# metium_rfm69.net
KiCad netlist of a schematic drawn in EAGLE
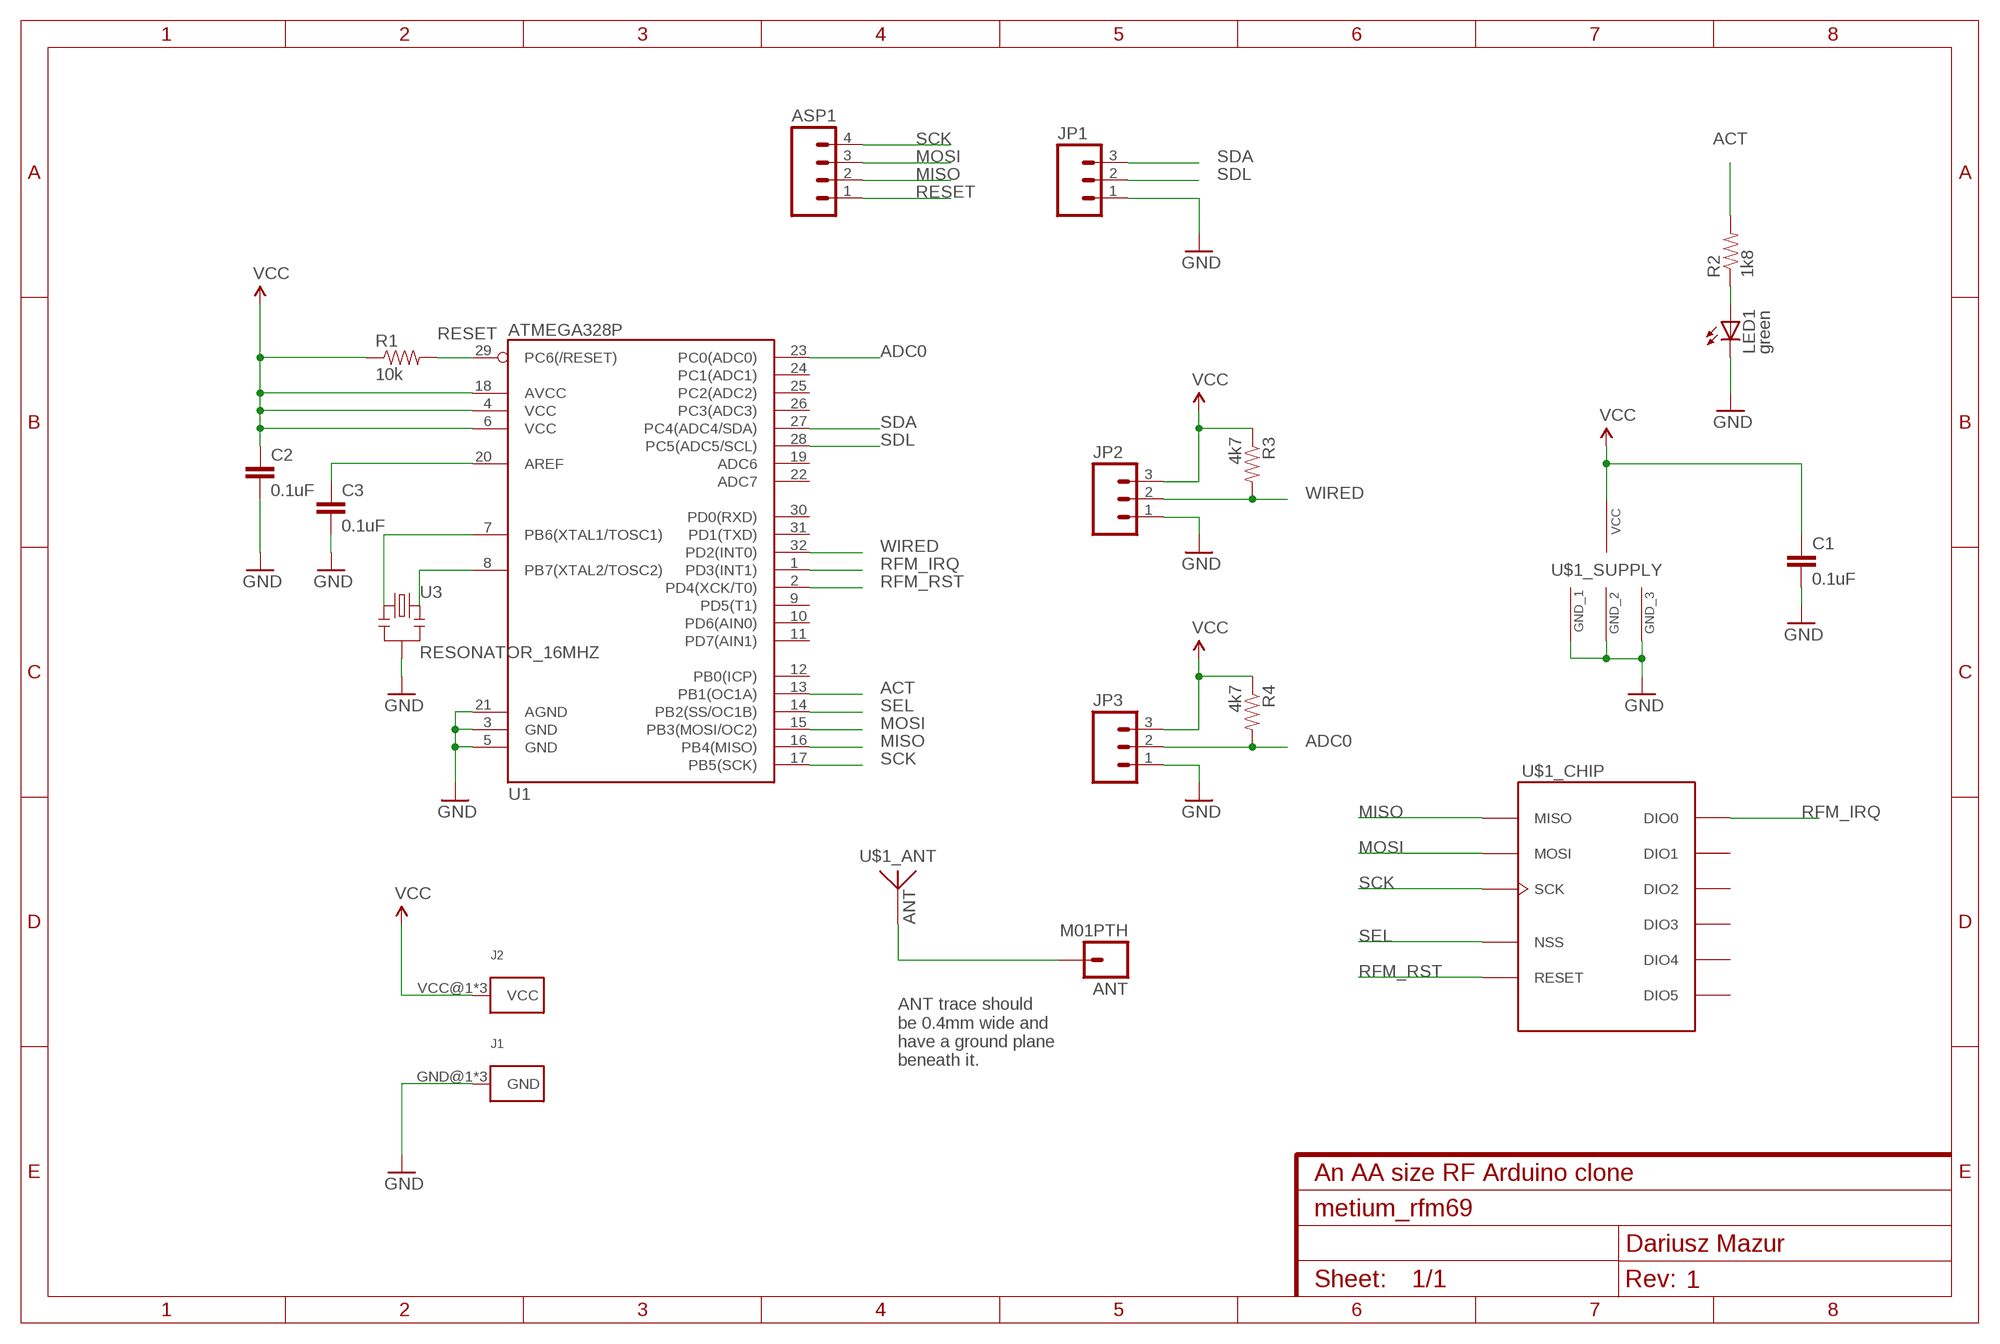
[diagram p0: schematic, sheet 1]

(export (version "E")
  (design (tool "Eeschema 10.0.6"))
  (components
    (comp (ref "ANT")
      (value "M01PTH")
      (footprint "eagle-import:1X01")
      (libsource (lib "eagle-import") (part "M01PTH"))
    )
    (comp (ref "ASP1")
      (value "M04PTH")
      (footprint "eagle-import:1X04")
      (libsource (lib "eagle-import") (part "M04PTH"))
    )
    (comp (ref "C1")
      (value "0.1uF")
      (footprint "eagle-import:0603-CAP")
      (libsource (lib "eagle-import") (part "0.1UF-25V(+80/-20%)(0603)"))
    )
    (comp (ref "C2")
      (value "0.1uF")
      (footprint "eagle-import:0603-CAP")
      (libsource (lib "eagle-import") (part "0.1UF-25V(+80/-20%)(0603)"))
    )
    (comp (ref "C3")
      (value "0.1uF")
      (footprint "eagle-import:0603-CAP")
      (libsource (lib "eagle-import") (part "0.1UF-25V(+80/-20%)(0603)"))
    )
    (comp (ref "J1")
      (value "KEYSTONE-629")
      (footprint "eagle-import:KEYSTONE_AA_AAA_BATTERY_TERMINAL-629")
      (libsource (lib "eagle-import") (part "KEYSTONE-629"))
    )
    (comp (ref "J2")
      (value "KEYSTONE-637")
      (footprint "eagle-import:KEYSTONE_AA_AAA_BATTERY_TERMINAL-637")
      (libsource (lib "eagle-import") (part "KEYSTONE-637"))
    )
    (comp (ref "JP1")
      (value "M03PTH")
      (footprint "eagle-import:1X03")
      (libsource (lib "eagle-import") (part "M03PTH"))
    )
    (comp (ref "JP2")
      (value "M03PTH")
      (footprint "eagle-import:1X03")
      (libsource (lib "eagle-import") (part "M03PTH"))
    )
    (comp (ref "JP3")
      (value "M03PTH")
      (footprint "eagle-import:1X03")
      (libsource (lib "eagle-import") (part "M03PTH"))
    )
    (comp (ref "LED1")
      (value "green")
      (footprint "eagle-import:LED-0603")
      (libsource (lib "eagle-import") (part "LED0603"))
    )
    (comp (ref "R1")
      (value "10k")
      (footprint "eagle-import:0603-RES")
      (libsource (lib "eagle-import") (part "RESISTOR0603-RES"))
    )
    (comp (ref "R2")
      (value "1k8")
      (footprint "eagle-import:0603-RES")
      (libsource (lib "eagle-import") (part "RESISTOR0603-RES"))
    )
    (comp (ref "R3")
      (value "4k7")
      (footprint "eagle-import:0603-RES")
      (libsource (lib "eagle-import") (part "RESISTOR0603-RES"))
    )
    (comp (ref "R4")
      (value "4k7")
      (footprint "eagle-import:0603-RES")
      (libsource (lib "eagle-import") (part "RESISTOR0603-RES"))
    )
    (comp (ref "U$1")
      (value "RFM69HCW-S2")
      (footprint "eagle-import:HOPE-RF-16")
      (libsource (lib "eagle-import") (part "RFM69HCW-S2"))
    )
    (comp (ref "U1")
      (value "ATMEGA328P")
      (footprint "eagle-import:TQFP32-08")
      (libsource (lib "eagle-import") (part "ATMEGA328_SMT"))
    )
    (comp (ref "U3")
      (value "RESONATOR_16MHZ")
      (footprint "eagle-import:RESONATOR_SMD")
      (libsource (lib "eagle-import") (part "RESONATOR_16MHZ"))
    )
  )
  (nets
    (net (code "1") (name "/ACT") (class "Default")
      (node (ref "R2") (pin "2") (pinfunction "2_2") (pintype "passive"))
      (node (ref "U1") (pin "13") (pinfunction "PB1(OC1A)_13") (pintype "bidirectional"))
    )
    (net (code "2") (name "/ADC0") (class "Default")
      (node (ref "JP3") (pin "2") (pinfunction "2_2") (pintype "passive"))
      (node (ref "R4") (pin "2") (pinfunction "2_2") (pintype "passive"))
      (node (ref "U1") (pin "23") (pinfunction "PC0(ADC0)_23") (pintype "bidirectional"))
    )
    (net (code "3") (name "/MISO") (class "Default")
      (node (ref "ASP1") (pin "2") (pinfunction "2_2") (pintype "passive"))
      (node (ref "U$1") (pin "MISO") (pinfunction "MISO_MISO") (pintype "input"))
      (node (ref "U1") (pin "16") (pinfunction "PB4(MISO)_16") (pintype "bidirectional"))
    )
    (net (code "4") (name "/MOSI") (class "Default")
      (node (ref "ASP1") (pin "3") (pinfunction "3_3") (pintype "passive"))
      (node (ref "U$1") (pin "MOSI") (pinfunction "MOSI_MOSI") (pintype "output"))
      (node (ref "U1") (pin "15") (pinfunction "PB3(MOSI/OC2)_15") (pintype "bidirectional"))
    )
    (net (code "5") (name "/RESET") (class "Default")
      (node (ref "ASP1") (pin "1") (pinfunction "1_1") (pintype "passive"))
      (node (ref "R1") (pin "2") (pinfunction "2_2") (pintype "passive"))
      (node (ref "U1") (pin "29") (pinfunction "PC6(/RESET)_29") (pintype "bidirectional"))
    )
    (net (code "6") (name "/RFM_IRQ") (class "Default")
      (node (ref "U$1") (pin "DIO0") (pinfunction "DIO0_DIO0") (pintype "bidirectional"))
      (node (ref "U1") (pin "1") (pinfunction "PD3(INT1)_1") (pintype "bidirectional"))
    )
    (net (code "7") (name "/RFM_RST") (class "Default")
      (node (ref "U$1") (pin "RESET") (pinfunction "RESET_RESET") (pintype "bidirectional"))
      (node (ref "U1") (pin "2") (pinfunction "PD4(XCK/T0)_2") (pintype "bidirectional"))
    )
    (net (code "8") (name "/SCK") (class "Default")
      (node (ref "ASP1") (pin "4") (pinfunction "4_4") (pintype "passive"))
      (node (ref "U$1") (pin "SCK") (pinfunction "SCK_SCK") (pintype "input"))
      (node (ref "U1") (pin "17") (pinfunction "PB5(SCK)_17") (pintype "bidirectional"))
    )
    (net (code "9") (name "/SDA") (class "Default")
      (node (ref "JP1") (pin "3") (pinfunction "3_3") (pintype "passive"))
      (node (ref "U1") (pin "27") (pinfunction "PC4(ADC4/SDA)_27") (pintype "bidirectional"))
    )
    (net (code "10") (name "/SDL") (class "Default")
      (node (ref "JP1") (pin "2") (pinfunction "2_2") (pintype "passive"))
      (node (ref "U1") (pin "28") (pinfunction "PC5(ADC5/SCL)_28") (pintype "bidirectional"))
    )
    (net (code "11") (name "/SEL") (class "Default")
      (node (ref "U$1") (pin "NSS") (pinfunction "NSS_NSS") (pintype "input"))
      (node (ref "U1") (pin "14") (pinfunction "PB2(SS/OC1B)_14") (pintype "bidirectional"))
    )
    (net (code "12") (name "/WIRED") (class "Default")
      (node (ref "JP2") (pin "2") (pinfunction "2_2") (pintype "passive"))
      (node (ref "R3") (pin "2") (pinfunction "2_2") (pintype "passive"))
      (node (ref "U1") (pin "32") (pinfunction "PD2(INT0)_32") (pintype "bidirectional"))
    )
    (net (code "13") (name "GND") (class "Default")
      (node (ref "C1") (pin "2") (pinfunction "2_2") (pintype "passive"))
      (node (ref "C2") (pin "2") (pinfunction "2_2") (pintype "passive"))
      (node (ref "C3") (pin "2") (pinfunction "2_2") (pintype "passive"))
      (node (ref "J1") (pin "GND@1") (pinfunction "GND_GND@1") (pintype "power_in"))
      (node (ref "J1") (pin "GND@2") (pinfunction "GND_GND@2") (pintype "power_in"))
      (node (ref "J1") (pin "GND@3") (pinfunction "GND_GND@3") (pintype "power_in"))
      (node (ref "JP1") (pin "1") (pinfunction "1_1") (pintype "passive"))
      (node (ref "JP2") (pin "1") (pinfunction "1_1") (pintype "passive"))
      (node (ref "JP3") (pin "1") (pinfunction "1_1") (pintype "passive"))
      (node (ref "LED1") (pin "C") (pinfunction "C_C") (pintype "passive"))
      (node (ref "U$1") (pin "GND1") (pinfunction "GND_1_GND1") (pintype "power_in"))
      (node (ref "U$1") (pin "GND2") (pinfunction "GND_2_GND2") (pintype "power_in"))
      (node (ref "U$1") (pin "GND3") (pinfunction "GND_3_GND3") (pintype "power_in"))
      (node (ref "U1") (pin "21") (pinfunction "AGND_21") (pintype "bidirectional"))
      (node (ref "U1") (pin "3") (pinfunction "GND_3") (pintype "bidirectional"))
      (node (ref "U1") (pin "5") (pinfunction "GND_5") (pintype "bidirectional"))
      (node (ref "U3") (pin "2") (pinfunction "2_2") (pintype "passive"))
    )
    (net (code "14") (name "Net-(ANT-Pad1)") (class "Default")
      (node (ref "ANT") (pin "1") (pinfunction "1_1") (pintype "passive"))
      (node (ref "U$1") (pin "ANT") (pinfunction "ANT_ANT") (pintype "passive"))
    )
    (net (code "15") (name "Net-(LED1-PadA)") (class "Default")
      (node (ref "LED1") (pin "A") (pinfunction "A_A") (pintype "passive"))
      (node (ref "R2") (pin "1") (pinfunction "1_1") (pintype "passive"))
    )
    (net (code "16") (name "Net-(U1-AREF)") (class "Default")
      (node (ref "C3") (pin "1") (pinfunction "1_1") (pintype "passive"))
      (node (ref "U1") (pin "20") (pinfunction "AREF_20") (pintype "bidirectional"))
    )
    (net (code "17") (name "Net-(U1-PB6(XTAL1{slash}TOSC1))") (class "Default")
      (node (ref "U1") (pin "7") (pinfunction "PB6(XTAL1/TOSC1)_7") (pintype "bidirectional"))
      (node (ref "U3") (pin "1") (pinfunction "1_1") (pintype "passive"))
    )
    (net (code "18") (name "Net-(U1-PB7(XTAL2{slash}TOSC2))") (class "Default")
      (node (ref "U1") (pin "8") (pinfunction "PB7(XTAL2/TOSC2)_8") (pintype "bidirectional"))
      (node (ref "U3") (pin "3") (pinfunction "3_3") (pintype "passive"))
    )
    (net (code "19") (name "VCC") (class "Default")
      (node (ref "C1") (pin "1") (pinfunction "1_1") (pintype "passive"))
      (node (ref "C2") (pin "1") (pinfunction "1_1") (pintype "passive"))
      (node (ref "J2") (pin "VCC@1") (pinfunction "VCC_VCC@1") (pintype "power_in"))
      (node (ref "J2") (pin "VCC@2") (pinfunction "VCC_VCC@2") (pintype "power_in"))
      (node (ref "J2") (pin "VCC@3") (pinfunction "VCC_VCC@3") (pintype "power_in"))
      (node (ref "JP2") (pin "3") (pinfunction "3_3") (pintype "passive"))
      (node (ref "JP3") (pin "3") (pinfunction "3_3") (pintype "passive"))
      (node (ref "R1") (pin "1") (pinfunction "1_1") (pintype "passive"))
      (node (ref "R3") (pin "1") (pinfunction "1_1") (pintype "passive"))
      (node (ref "R4") (pin "1") (pinfunction "1_1") (pintype "passive"))
      (node (ref "U$1") (pin "3.3V") (pinfunction "VCC_3.3V") (pintype "power_in"))
      (node (ref "U1") (pin "18") (pinfunction "AVCC_18") (pintype "bidirectional"))
      (node (ref "U1") (pin "4") (pinfunction "VCC_4") (pintype "bidirectional"))
      (node (ref "U1") (pin "6") (pinfunction "VCC_6") (pintype "bidirectional"))
    )
    (net (code "20") (name "unconnected-(U$1-PadDIO1)") (class "Default")
      (node (ref "U$1") (pin "DIO1") (pinfunction "DIO1_DIO1") (pintype "bidirectional"))
    )
    (net (code "21") (name "unconnected-(U$1-PadDIO2)") (class "Default")
      (node (ref "U$1") (pin "DIO2") (pinfunction "DIO2_DIO2") (pintype "bidirectional"))
    )
    (net (code "22") (name "unconnected-(U$1-PadDIO3)") (class "Default")
      (node (ref "U$1") (pin "DIO3") (pinfunction "DIO3_DIO3") (pintype "bidirectional"))
    )
    (net (code "23") (name "unconnected-(U$1-PadDIO4)") (class "Default")
      (node (ref "U$1") (pin "DIO4") (pinfunction "DIO4_DIO4") (pintype "bidirectional"))
    )
    (net (code "24") (name "unconnected-(U$1-PadDIO5)") (class "Default")
      (node (ref "U$1") (pin "DIO5") (pinfunction "DIO5_DIO5") (pintype "bidirectional"))
    )
    (net (code "25") (name "unconnected-(U1-ADC6-Pad19)") (class "Default")
      (node (ref "U1") (pin "19") (pinfunction "ADC6_19") (pintype "bidirectional"))
    )
    (net (code "26") (name "unconnected-(U1-ADC7-Pad22)") (class "Default")
      (node (ref "U1") (pin "22") (pinfunction "ADC7_22") (pintype "bidirectional"))
    )
    (net (code "27") (name "unconnected-(U1-PB0(ICP)-Pad12)") (class "Default")
      (node (ref "U1") (pin "12") (pinfunction "PB0(ICP)_12") (pintype "bidirectional"))
    )
    (net (code "28") (name "unconnected-(U1-PC1(ADC1)-Pad24)") (class "Default")
      (node (ref "U1") (pin "24") (pinfunction "PC1(ADC1)_24") (pintype "bidirectional"))
    )
    (net (code "29") (name "unconnected-(U1-PC2(ADC2)-Pad25)") (class "Default")
      (node (ref "U1") (pin "25") (pinfunction "PC2(ADC2)_25") (pintype "bidirectional"))
    )
    (net (code "30") (name "unconnected-(U1-PC3(ADC3)-Pad26)") (class "Default")
      (node (ref "U1") (pin "26") (pinfunction "PC3(ADC3)_26") (pintype "bidirectional"))
    )
    (net (code "31") (name "unconnected-(U1-PD0(RXD)-Pad30)") (class "Default")
      (node (ref "U1") (pin "30") (pinfunction "PD0(RXD)_30") (pintype "bidirectional"))
    )
    (net (code "32") (name "unconnected-(U1-PD1(TXD)-Pad31)") (class "Default")
      (node (ref "U1") (pin "31") (pinfunction "PD1(TXD)_31") (pintype "bidirectional"))
    )
    (net (code "33") (name "unconnected-(U1-PD5(T1)-Pad9)") (class "Default")
      (node (ref "U1") (pin "9") (pinfunction "PD5(T1)_9") (pintype "bidirectional"))
    )
    (net (code "34") (name "unconnected-(U1-PD6(AIN0)-Pad10)") (class "Default")
      (node (ref "U1") (pin "10") (pinfunction "PD6(AIN0)_10") (pintype "bidirectional"))
    )
    (net (code "35") (name "unconnected-(U1-PD7(AIN1)-Pad11)") (class "Default")
      (node (ref "U1") (pin "11") (pinfunction "PD7(AIN1)_11") (pintype "bidirectional"))
    )
  )
)
